# OpenHAS_OutputBoard_v1_0.net
KiCad netlist of a schematic drawn in EAGLE
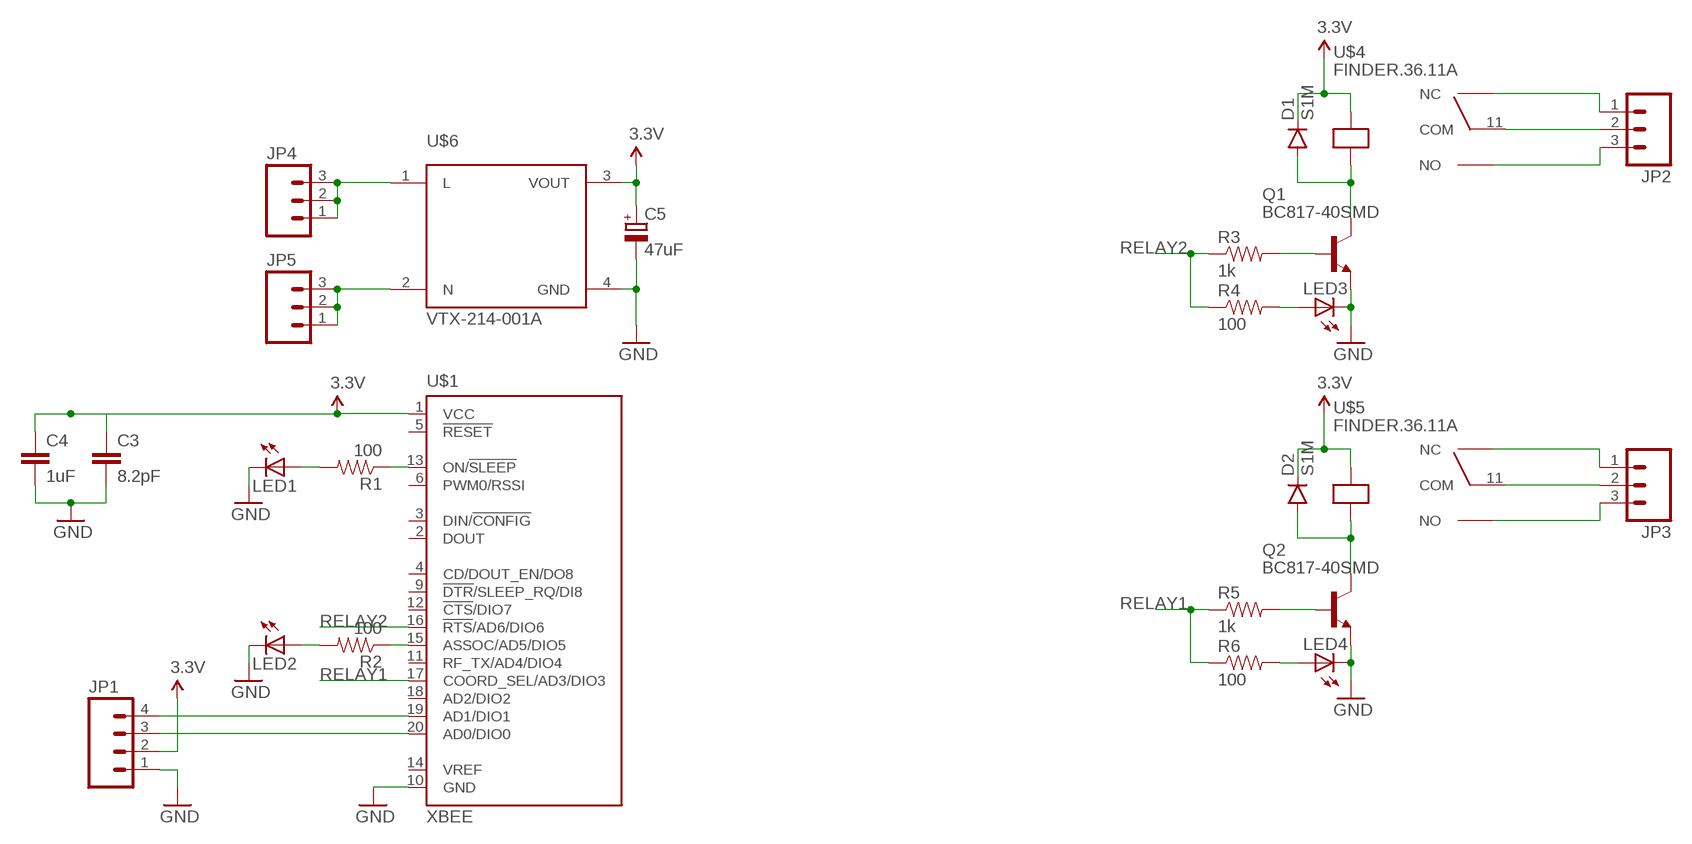
[diagram p0: schematic, sheet 1]

(export (version "E")
  (design (tool "Eeschema 10.0.6"))
  (components
    (comp (ref "C3")
      (value "8.2pF")
      (footprint "eagle-import:0805")
      (libsource (lib "eagle-import") (part "CAP0805"))
    )
    (comp (ref "C4")
      (value "1uF")
      (footprint "eagle-import:0805")
      (libsource (lib "eagle-import") (part "CAP0805"))
    )
    (comp (ref "C5")
      (value "47uF")
      (footprint "eagle-import:E2-5")
      (libsource (lib "eagle-import") (part "CPOL-EUE2-5"))
    )
    (comp (ref "D1")
      (value "S1M")
      (footprint "eagle-import:SMA-DIODE")
      (libsource (lib "eagle-import") (part "DIODESMA"))
    )
    (comp (ref "D2")
      (value "S1M")
      (footprint "eagle-import:SMA-DIODE")
      (libsource (lib "eagle-import") (part "DIODESMA"))
    )
    (comp (ref "JP1")
      (value "M04SCREW")
      (footprint "eagle-import:SCREWTERMINAL-3.5MM-4")
      (libsource (lib "eagle-import") (part "M04SCREW"))
    )
    (comp (ref "JP2")
      (value "M03-SCREW-5MM")
      (footprint "eagle-import:SCREWTERMINAL-5MM-3")
      (libsource (lib "eagle-import") (part "M03-SCREW-5MM"))
    )
    (comp (ref "JP3")
      (value "M03-SCREW-5MM")
      (footprint "eagle-import:SCREWTERMINAL-5MM-3")
      (libsource (lib "eagle-import") (part "M03-SCREW-5MM"))
    )
    (comp (ref "JP4")
      (value "M03-SCREW-5MM")
      (footprint "eagle-import:SCREWTERMINAL-5MM-3")
      (libsource (lib "eagle-import") (part "M03-SCREW-5MM"))
    )
    (comp (ref "JP5")
      (value "M03-SCREW-5MM")
      (footprint "eagle-import:SCREWTERMINAL-5MM-3")
      (libsource (lib "eagle-import") (part "M03-SCREW-5MM"))
    )
    (comp (ref "LED1")
      (value "LEDCHIP-LED0805")
      (footprint "eagle-import:CHIP-LED0805")
      (libsource (lib "eagle-import") (part "LEDCHIP-LED0805"))
    )
    (comp (ref "LED2")
      (value "LEDCHIP-LED0805")
      (footprint "eagle-import:CHIP-LED0805")
      (libsource (lib "eagle-import") (part "LEDCHIP-LED0805"))
    )
    (comp (ref "LED3")
      (value "LEDCHIP-LED0805")
      (footprint "eagle-import:CHIP-LED0805")
      (libsource (lib "eagle-import") (part "LEDCHIP-LED0805"))
    )
    (comp (ref "LED4")
      (value "LEDCHIP-LED0805")
      (footprint "eagle-import:CHIP-LED0805")
      (libsource (lib "eagle-import") (part "LEDCHIP-LED0805"))
    )
    (comp (ref "Q1")
      (value "BC817-40SMD")
      (footprint "eagle-import:SOT23-BEC")
      (libsource (lib "eagle-import") (part "BC817SMD-40"))
    )
    (comp (ref "Q2")
      (value "BC817-40SMD")
      (footprint "eagle-import:SOT23-BEC")
      (libsource (lib "eagle-import") (part "BC817SMD-40"))
    )
    (comp (ref "R1")
      (value "100")
      (footprint "eagle-import:0805")
      (libsource (lib "eagle-import") (part "RESISTOR0805-RES"))
    )
    (comp (ref "R2")
      (value "100")
      (footprint "eagle-import:0805")
      (libsource (lib "eagle-import") (part "RESISTOR0805-RES"))
    )
    (comp (ref "R3")
      (value "1k")
      (footprint "eagle-import:0805")
      (libsource (lib "eagle-import") (part "SparkFun-Resistors_RESISTOR0805-RES"))
    )
    (comp (ref "R4")
      (value "100")
      (footprint "eagle-import:0805")
      (libsource (lib "eagle-import") (part "RESISTOR0805-RES"))
    )
    (comp (ref "R5")
      (value "1k")
      (footprint "eagle-import:0805")
      (libsource (lib "eagle-import") (part "SparkFun-Resistors_RESISTOR0805-RES"))
    )
    (comp (ref "R6")
      (value "100")
      (footprint "eagle-import:0805")
      (libsource (lib "eagle-import") (part "RESISTOR0805-RES"))
    )
    (comp (ref "U$1")
      (value "XBEE")
      (footprint "eagle-import:XBEE")
      (fields (field (name "MPN") "XBP24-Z7UIT-004"))
      (libsource (lib "eagle-import") (part "XBEE"))
    )
    (comp (ref "U$4")
      (value "FINDER.36.11A")
      (footprint "eagle-import:31.11")
      (libsource (lib "eagle-import") (part "FINDER.36.11A"))
    )
    (comp (ref "U$5")
      (value "FINDER.36.11A")
      (footprint "eagle-import:31.11")
      (libsource (lib "eagle-import") (part "FINDER.36.11A"))
    )
    (comp (ref "U$6")
      (value "VTX-214-001A")
      (footprint "eagle-import:VTX-214-003-X")
      (libsource (lib "eagle-import") (part "VTX-214-001A"))
    )
  )
  (nets
    (net (code "1") (name "/RELAY1") (class "Default")
      (node (ref "R5") (pin "1") (pinfunction "1_1") (pintype "passive"))
      (node (ref "R6") (pin "1") (pinfunction "1_1") (pintype "passive"))
      (node (ref "U$1") (pin "17") (pinfunction "COORD_SEL/AD3/DIO3_17") (pintype "bidirectional"))
    )
    (net (code "2") (name "/RELAY2") (class "Default")
      (node (ref "R3") (pin "1") (pinfunction "1_1") (pintype "passive"))
      (node (ref "R4") (pin "1") (pinfunction "1_1") (pintype "passive"))
      (node (ref "U$1") (pin "16") (pinfunction "~{RTS}/AD6/DIO6_16") (pintype "bidirectional"))
    )
    (net (code "3") (name "3.3V") (class "Default")
      (node (ref "C3") (pin "1") (pinfunction "1_1") (pintype "passive"))
      (node (ref "C4") (pin "1") (pinfunction "1_1") (pintype "passive"))
      (node (ref "C5") (pin "+") (pinfunction "+_+") (pintype "passive"))
      (node (ref "D1") (pin "C") (pinfunction "C_C") (pintype "passive"))
      (node (ref "D2") (pin "C") (pinfunction "C_C") (pintype "passive"))
      (node (ref "JP1") (pin "2") (pinfunction "2_2") (pintype "passive"))
      (node (ref "U$1") (pin "1") (pinfunction "VCC_1") (pintype "power_in"))
      (node (ref "U$4") (pin "A1") (pinfunction "A1_A1") (pintype "bidirectional"))
      (node (ref "U$5") (pin "A1") (pinfunction "A1_A1") (pintype "bidirectional"))
      (node (ref "U$6") (pin "3") (pinfunction "VOUT_3") (pintype "bidirectional"))
    )
    (net (code "4") (name "GND") (class "Default")
      (node (ref "C3") (pin "2") (pinfunction "2_2") (pintype "passive"))
      (node (ref "C4") (pin "2") (pinfunction "2_2") (pintype "passive"))
      (node (ref "C5") (pin "-") (pinfunction "-_-") (pintype "passive"))
      (node (ref "JP1") (pin "1") (pinfunction "1_1") (pintype "passive"))
      (node (ref "LED1") (pin "C") (pinfunction "C_C") (pintype "passive"))
      (node (ref "LED2") (pin "C") (pinfunction "C_C") (pintype "passive"))
      (node (ref "LED3") (pin "C") (pinfunction "C_C") (pintype "passive"))
      (node (ref "LED4") (pin "C") (pinfunction "C_C") (pintype "passive"))
      (node (ref "Q1") (pin "E") (pinfunction "E_E") (pintype "passive"))
      (node (ref "Q2") (pin "E") (pinfunction "E_E") (pintype "passive"))
      (node (ref "U$1") (pin "10") (pinfunction "GND_10") (pintype "power_in"))
      (node (ref "U$6") (pin "4") (pinfunction "GND_4") (pintype "bidirectional"))
    )
    (net (code "5") (name "Net-(D1-PadA)") (class "Default")
      (node (ref "D1") (pin "A") (pinfunction "A_A") (pintype "passive"))
      (node (ref "Q1") (pin "C") (pinfunction "C_C") (pintype "passive"))
      (node (ref "U$4") (pin "A2") (pinfunction "A2_A2") (pintype "bidirectional"))
    )
    (net (code "6") (name "Net-(D2-PadA)") (class "Default")
      (node (ref "D2") (pin "A") (pinfunction "A_A") (pintype "passive"))
      (node (ref "Q2") (pin "C") (pinfunction "C_C") (pintype "passive"))
      (node (ref "U$5") (pin "A2") (pinfunction "A2_A2") (pintype "bidirectional"))
    )
    (net (code "7") (name "Net-(LED1-PadA)") (class "Default")
      (node (ref "LED1") (pin "A") (pinfunction "A_A") (pintype "passive"))
      (node (ref "R1") (pin "2") (pinfunction "2_2") (pintype "passive"))
    )
    (net (code "8") (name "Net-(LED2-PadA)") (class "Default")
      (node (ref "LED2") (pin "A") (pinfunction "A_A") (pintype "passive"))
      (node (ref "R2") (pin "2") (pinfunction "2_2") (pintype "passive"))
    )
    (net (code "9") (name "Net-(LED3-PadA)") (class "Default")
      (node (ref "LED3") (pin "A") (pinfunction "A_A") (pintype "passive"))
      (node (ref "R4") (pin "2") (pinfunction "2_2") (pintype "passive"))
    )
    (net (code "10") (name "Net-(LED4-PadA)") (class "Default")
      (node (ref "LED4") (pin "A") (pinfunction "A_A") (pintype "passive"))
      (node (ref "R6") (pin "2") (pinfunction "2_2") (pintype "passive"))
    )
    (net (code "11") (name "Net-(Q1-PadB)") (class "Default")
      (node (ref "Q1") (pin "B") (pinfunction "B_B") (pintype "passive"))
      (node (ref "R3") (pin "2") (pinfunction "2_2") (pintype "passive"))
    )
    (net (code "12") (name "Net-(Q2-PadB)") (class "Default")
      (node (ref "Q2") (pin "B") (pinfunction "B_B") (pintype "passive"))
      (node (ref "R5") (pin "2") (pinfunction "2_2") (pintype "passive"))
    )
    (net (code "13") (name "Net-(U$1-AD0{slash}DIO0)") (class "Default")
      (node (ref "JP1") (pin "3") (pinfunction "3_3") (pintype "passive"))
      (node (ref "U$1") (pin "20") (pinfunction "AD0/DIO0_20") (pintype "bidirectional"))
    )
    (net (code "14") (name "Net-(U$1-AD1{slash}DIO1)") (class "Default")
      (node (ref "JP1") (pin "4") (pinfunction "4_4") (pintype "passive"))
      (node (ref "U$1") (pin "19") (pinfunction "AD1/DIO1_19") (pintype "bidirectional"))
    )
    (net (code "15") (name "Net-(U$1-ASSOC{slash}AD5{slash}DIO5)") (class "Default")
      (node (ref "R2") (pin "1") (pinfunction "1_1") (pintype "passive"))
      (node (ref "U$1") (pin "15") (pinfunction "ASSOC/AD5/DIO5_15") (pintype "bidirectional"))
    )
    (net (code "16") (name "Net-(U$1-ON{slash}~{SLEEP})") (class "Default")
      (node (ref "R1") (pin "1") (pinfunction "1_1") (pintype "passive"))
      (node (ref "U$1") (pin "13") (pinfunction "ON/~{SLEEP}_13") (pintype "output"))
    )
    (net (code "17") (name "Net-(U$4-COM)") (class "Default")
      (node (ref "JP2") (pin "2") (pinfunction "2_2") (pintype "passive"))
      (node (ref "U$4") (pin "11") (pinfunction "COM_11") (pintype "bidirectional"))
    )
    (net (code "18") (name "Net-(U$4-NC)") (class "Default")
      (node (ref "JP2") (pin "1") (pinfunction "1_1") (pintype "passive"))
      (node (ref "U$4") (pin "12") (pinfunction "NC_12") (pintype "bidirectional"))
    )
    (net (code "19") (name "Net-(U$4-NO)") (class "Default")
      (node (ref "JP2") (pin "3") (pinfunction "3_3") (pintype "passive"))
      (node (ref "U$4") (pin "14") (pinfunction "NO_14") (pintype "bidirectional"))
    )
    (net (code "20") (name "Net-(U$5-COM)") (class "Default")
      (node (ref "JP3") (pin "2") (pinfunction "2_2") (pintype "passive"))
      (node (ref "U$5") (pin "11") (pinfunction "COM_11") (pintype "bidirectional"))
    )
    (net (code "21") (name "Net-(U$5-NC)") (class "Default")
      (node (ref "JP3") (pin "1") (pinfunction "1_1") (pintype "passive"))
      (node (ref "U$5") (pin "12") (pinfunction "NC_12") (pintype "bidirectional"))
    )
    (net (code "22") (name "Net-(U$5-NO)") (class "Default")
      (node (ref "JP3") (pin "3") (pinfunction "3_3") (pintype "passive"))
      (node (ref "U$5") (pin "14") (pinfunction "NO_14") (pintype "bidirectional"))
    )
    (net (code "23") (name "Net-(U$6-L)") (class "Default")
      (node (ref "JP4") (pin "1") (pinfunction "1_1") (pintype "passive"))
      (node (ref "JP4") (pin "2") (pinfunction "2_2") (pintype "passive"))
      (node (ref "JP4") (pin "3") (pinfunction "3_3") (pintype "passive"))
      (node (ref "U$6") (pin "1") (pinfunction "L_1") (pintype "bidirectional"))
    )
    (net (code "24") (name "Net-(U$6-N)") (class "Default")
      (node (ref "JP5") (pin "1") (pinfunction "1_1") (pintype "passive"))
      (node (ref "JP5") (pin "2") (pinfunction "2_2") (pintype "passive"))
      (node (ref "JP5") (pin "3") (pinfunction "3_3") (pintype "passive"))
      (node (ref "U$6") (pin "2") (pinfunction "N_2") (pintype "bidirectional"))
    )
    (net (code "25") (name "unconnected-(U$1-AD2{slash}DIO2-Pad18)") (class "Default")
      (node (ref "U$1") (pin "18") (pinfunction "AD2/DIO2_18") (pintype "bidirectional"))
    )
    (net (code "26") (name "unconnected-(U$1-CD{slash}DOUT_EN{slash}DO8-Pad4)") (class "Default")
      (node (ref "U$1") (pin "4") (pinfunction "CD/DOUT_EN/DO8_4") (pintype "output"))
    )
    (net (code "27") (name "unconnected-(U$1-DIN{slash}~{CONFIG}-Pad3)") (class "Default")
      (node (ref "U$1") (pin "3") (pinfunction "DIN/~{CONFIG}_3") (pintype "input"))
    )
    (net (code "28") (name "unconnected-(U$1-DOUT-Pad2)") (class "Default")
      (node (ref "U$1") (pin "2") (pinfunction "DOUT_2") (pintype "output"))
    )
    (net (code "29") (name "unconnected-(U$1-PWM0{slash}RSSI-Pad6)") (class "Default")
      (node (ref "U$1") (pin "6") (pinfunction "PWM0/RSSI_6") (pintype "output"))
    )
    (net (code "30") (name "unconnected-(U$1-RF_TX{slash}AD4{slash}DIO4-Pad11)") (class "Default")
      (node (ref "U$1") (pin "11") (pinfunction "RF_TX/AD4/DIO4_11") (pintype "bidirectional"))
    )
    (net (code "31") (name "unconnected-(U$1-VREF-Pad14)") (class "Default")
      (node (ref "U$1") (pin "14") (pinfunction "VREF_14") (pintype "input"))
    )
    (net (code "32") (name "unconnected-(U$1-~{CTS}{slash}DIO7-Pad12)") (class "Default")
      (node (ref "U$1") (pin "12") (pinfunction "~{CTS}/DIO7_12") (pintype "bidirectional"))
    )
    (net (code "33") (name "unconnected-(U$1-~{DTR}{slash}SLEEP_RQ{slash}DI8-Pad9)") (class "Default")
      (node (ref "U$1") (pin "9") (pinfunction "~{DTR}/SLEEP_RQ/DI8_9") (pintype "bidirectional"))
    )
    (net (code "34") (name "unconnected-(U$1-~{RESET}-Pad5)") (class "Default")
      (node (ref "U$1") (pin "5") (pinfunction "~{RESET}_5") (pintype "input"))
    )
  )
)
